# ShieldPi4_WS.net
KiCad netlist of a schematic drawn in EasyEDA
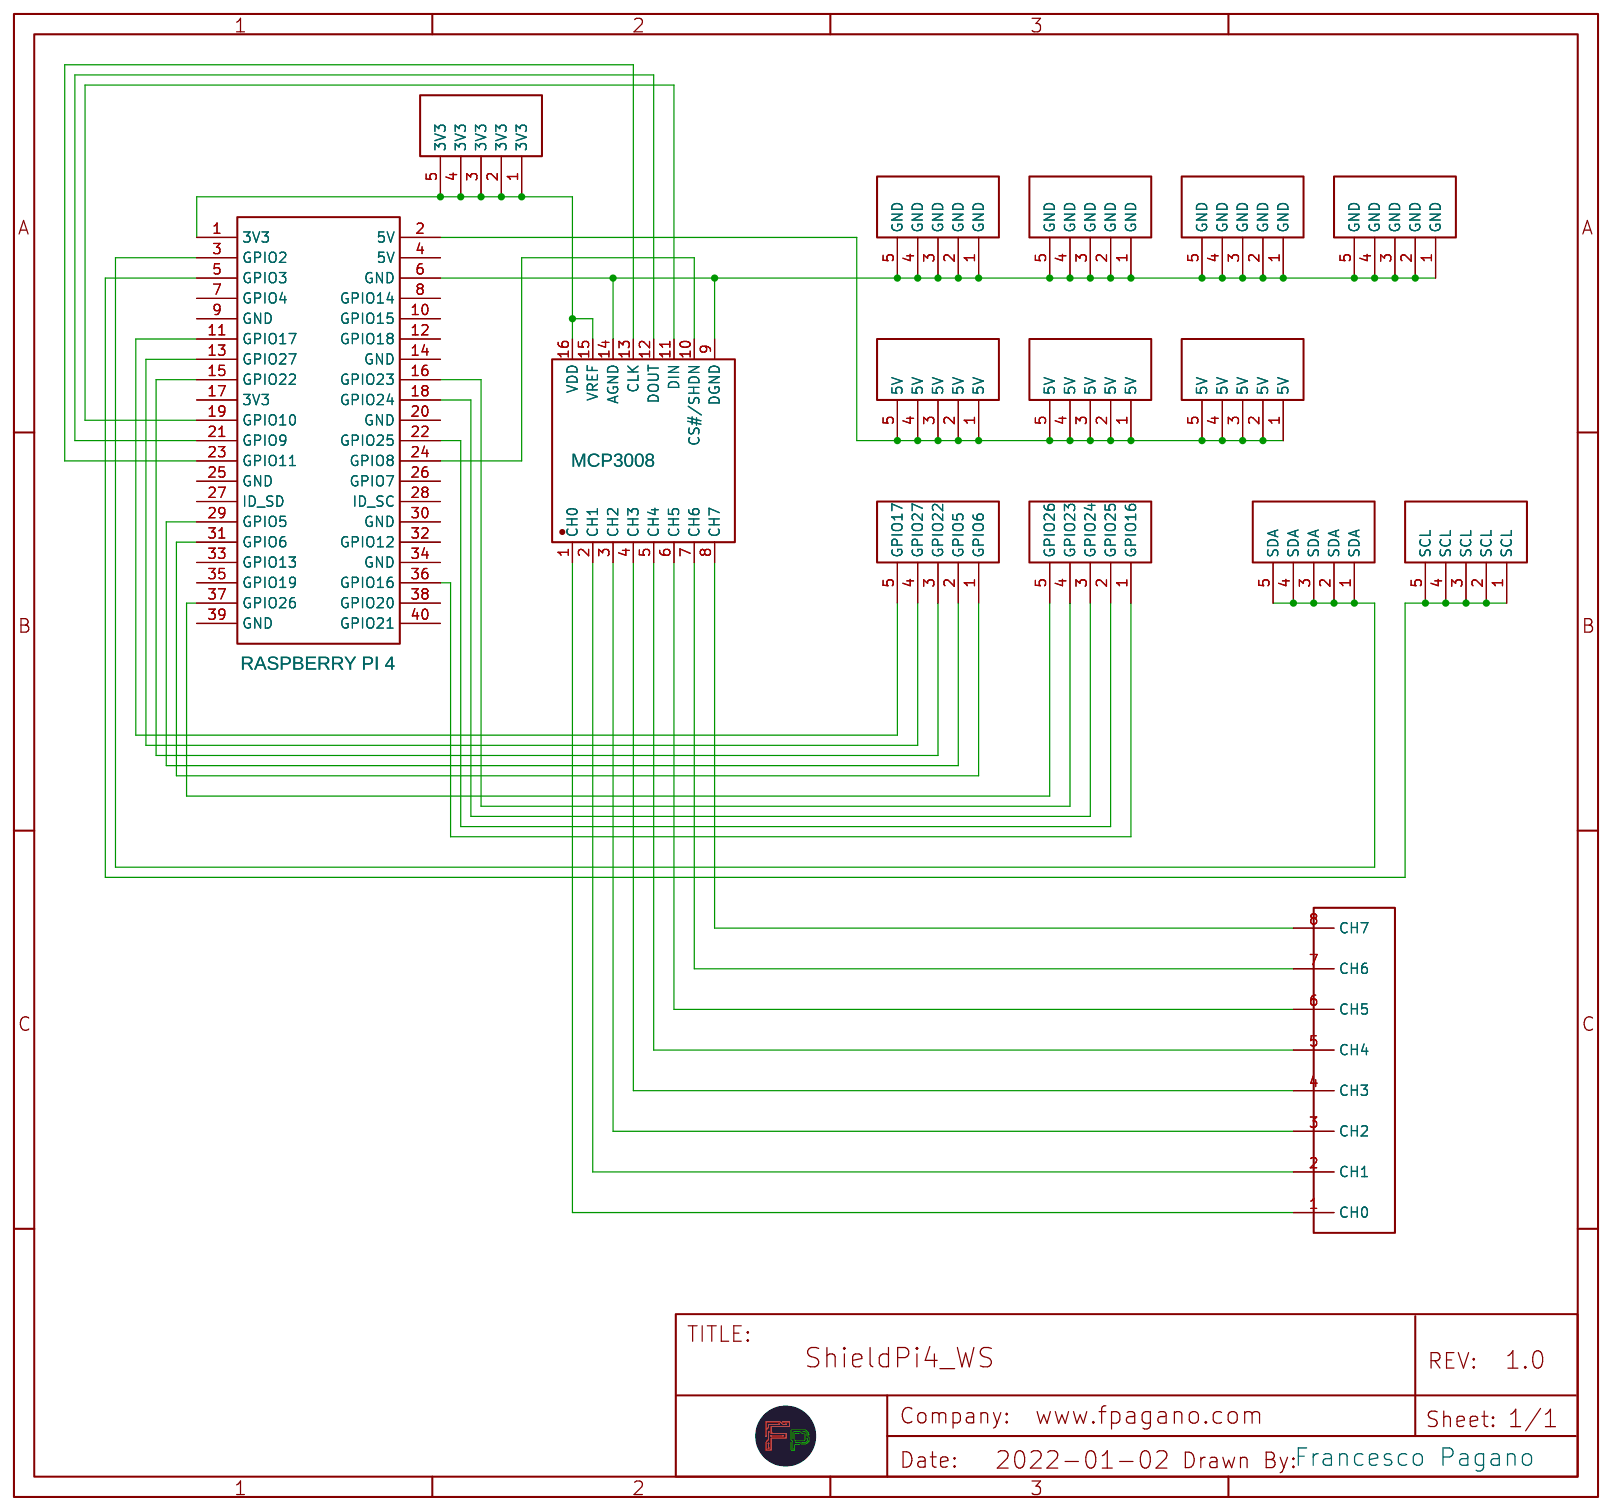
[diagram p0: schematic sheet]

(export (version "E")
  (design (tool "Eeschema 10.0.6"))
  (components
    (comp (ref "U1") (value "RASPBERRY PI 4") (libsource (lib "") (part "RASPBERRY PI 4")))
    (comp (ref "U2") (value "5 Pin Pinheader") (libsource (lib "") (part "5 Pin Pinheader_1")))
    (comp (ref "U3")
      (value "MCP3008")
      (fields
        (field (name "Manufacturer Part") "MCP3008-I/P")
        (field (name "Manufacturer") "MICROCHIP(美国微芯)")
      )
      (libsource (lib "") (part "MCP3008-I/P"))
    )
    (comp (ref "U4") (value "5 Pin Pinheader") (libsource (lib "") (part "5 Pin Pinheader_1")))
    (comp (ref "U5") (value "5 Pin Pinheader") (libsource (lib "") (part "5 Pin Pinheader_2")))
    (comp (ref "U6") (value "5 Pin Pinheader") (libsource (lib "") (part "5 Pin Pinheader_2")))
    (comp (ref "U7") (value "5 Pin Pinheader") (libsource (lib "") (part "5 Pin Pinheader_2")))
    (comp (ref "U8") (value "5 Pin Pinheader") (libsource (lib "") (part "5 Pin Pinheader_6")))
    (comp (ref "U9") (value "5 Pin Pinheader") (libsource (lib "") (part "5 Pin Pinheader_4")))
    (comp (ref "U10") (value "pinheader 2.54 - 8 pins") (libsource (lib "") (part "pinheader 2.54 - 8 pins")))
    (comp (ref "U11") (value "5 Pin Pinheader") (libsource (lib "") (part "5 Pin Pinheader_1")))
    (comp (ref "U12") (value "5 Pin Pinheader") (libsource (lib "") (part "5 Pin Pinheader_5")))
    (comp (ref "U13") (value "5 Pin Pinheader") (libsource (lib "") (part "5 Pin Pinheader_3")))
    (comp (ref "U15") (value "5 Pin Pinheader") (libsource (lib "") (part "5 Pin Pinheader")))
    (comp (ref "U16") (value "5 Pin Pinheader") (libsource (lib "") (part "5 Pin Pinheader_1")))
  )
  (nets
    (net (code "1") (name "Net-(U1-5V-Pad2)") (class "Default")
      (node (ref "U1") (pin "2") (pinfunction "5V_2") (pintype "unspecified"))
      (node (ref "U5") (pin "1") (pinfunction "5V_1") (pintype "unspecified"))
      (node (ref "U5") (pin "2") (pinfunction "5V_2") (pintype "unspecified"))
      (node (ref "U5") (pin "3") (pinfunction "5V_3") (pintype "unspecified"))
      (node (ref "U5") (pin "4") (pinfunction "5V_4") (pintype "unspecified"))
      (node (ref "U5") (pin "5") (pinfunction "5V_5") (pintype "unspecified"))
      (node (ref "U6") (pin "1") (pinfunction "5V_1") (pintype "unspecified"))
      (node (ref "U6") (pin "2") (pinfunction "5V_2") (pintype "unspecified"))
      (node (ref "U6") (pin "3") (pinfunction "5V_3") (pintype "unspecified"))
      (node (ref "U6") (pin "4") (pinfunction "5V_4") (pintype "unspecified"))
      (node (ref "U6") (pin "5") (pinfunction "5V_5") (pintype "unspecified"))
      (node (ref "U7") (pin "1") (pinfunction "5V_1") (pintype "unspecified"))
      (node (ref "U7") (pin "2") (pinfunction "5V_2") (pintype "unspecified"))
      (node (ref "U7") (pin "3") (pinfunction "5V_3") (pintype "unspecified"))
      (node (ref "U7") (pin "4") (pinfunction "5V_4") (pintype "unspecified"))
      (node (ref "U7") (pin "5") (pinfunction "5V_5") (pintype "unspecified"))
    )
    (net (code "2") (name "Net-(U1-GPIO2)") (class "Default")
      (node (ref "U1") (pin "3") (pinfunction "GPIO2_3") (pintype "unspecified"))
      (node (ref "U13") (pin "1") (pinfunction "SDA_1") (pintype "unspecified"))
      (node (ref "U13") (pin "2") (pinfunction "SDA_2") (pintype "unspecified"))
      (node (ref "U13") (pin "3") (pinfunction "SDA_3") (pintype "unspecified"))
      (node (ref "U13") (pin "4") (pinfunction "SDA_4") (pintype "unspecified"))
      (node (ref "U13") (pin "5") (pinfunction "SDA_5") (pintype "unspecified"))
    )
    (net (code "3") (name "Net-(U1-GPIO3)") (class "Default")
      (node (ref "U1") (pin "5") (pinfunction "GPIO3_5") (pintype "unspecified"))
      (node (ref "U12") (pin "1") (pinfunction "SCL_1") (pintype "unspecified"))
      (node (ref "U12") (pin "2") (pinfunction "SCL_2") (pintype "unspecified"))
      (node (ref "U12") (pin "3") (pinfunction "SCL_3") (pintype "unspecified"))
      (node (ref "U12") (pin "4") (pinfunction "SCL_4") (pintype "unspecified"))
      (node (ref "U12") (pin "5") (pinfunction "SCL_5") (pintype "unspecified"))
    )
    (net (code "4") (name "Net-(U1-GPIO5)") (class "Default")
      (node (ref "U1") (pin "29") (pinfunction "GPIO5_29") (pintype "unspecified"))
      (node (ref "U8") (pin "2") (pinfunction "GPIO5_2") (pintype "unspecified"))
    )
    (net (code "5") (name "Net-(U1-GPIO6)") (class "Default")
      (node (ref "U1") (pin "31") (pinfunction "GPIO6_31") (pintype "unspecified"))
      (node (ref "U8") (pin "1") (pinfunction "GPIO6_1") (pintype "unspecified"))
    )
    (net (code "6") (name "Net-(U1-GPIO8)") (class "Default")
      (node (ref "U1") (pin "24") (pinfunction "GPIO8_24") (pintype "unspecified"))
      (node (ref "U3") (pin "10") (pinfunction "CS#/SHDN_10") (pintype "unspecified"))
    )
    (net (code "7") (name "Net-(U1-GPIO9)") (class "Default")
      (node (ref "U1") (pin "21") (pinfunction "GPIO9_21") (pintype "unspecified"))
      (node (ref "U3") (pin "12") (pinfunction "DOUT_12") (pintype "unspecified"))
    )
    (net (code "8") (name "Net-(U1-GPIO10)") (class "Default")
      (node (ref "U1") (pin "19") (pinfunction "GPIO10_19") (pintype "unspecified"))
      (node (ref "U3") (pin "11") (pinfunction "DIN_11") (pintype "unspecified"))
    )
    (net (code "9") (name "Net-(U1-GPIO11)") (class "Default")
      (node (ref "U1") (pin "23") (pinfunction "GPIO11_23") (pintype "unspecified"))
      (node (ref "U3") (pin "13") (pinfunction "CLK_13") (pintype "unspecified"))
    )
    (net (code "10") (name "Net-(U1-GPIO16)") (class "Default")
      (node (ref "U1") (pin "36") (pinfunction "GPIO16_36") (pintype "unspecified"))
      (node (ref "U9") (pin "1") (pinfunction "GPIO16_1") (pintype "unspecified"))
    )
    (net (code "11") (name "Net-(U1-GPIO17)") (class "Default")
      (node (ref "U1") (pin "11") (pinfunction "GPIO17_11") (pintype "unspecified"))
      (node (ref "U8") (pin "5") (pinfunction "GPIO17_5") (pintype "unspecified"))
    )
    (net (code "12") (name "Net-(U1-GPIO22)") (class "Default")
      (node (ref "U1") (pin "15") (pinfunction "GPIO22_15") (pintype "unspecified"))
      (node (ref "U8") (pin "3") (pinfunction "GPIO22_3") (pintype "unspecified"))
    )
    (net (code "13") (name "Net-(U1-GPIO23)") (class "Default")
      (node (ref "U1") (pin "16") (pinfunction "GPIO23_16") (pintype "unspecified"))
      (node (ref "U9") (pin "4") (pinfunction "GPIO23_4") (pintype "unspecified"))
    )
    (net (code "14") (name "Net-(U1-GPIO24)") (class "Default")
      (node (ref "U1") (pin "18") (pinfunction "GPIO24_18") (pintype "unspecified"))
      (node (ref "U9") (pin "3") (pinfunction "GPIO24_3") (pintype "unspecified"))
    )
    (net (code "15") (name "Net-(U1-GPIO25)") (class "Default")
      (node (ref "U1") (pin "22") (pinfunction "GPIO25_22") (pintype "unspecified"))
      (node (ref "U9") (pin "2") (pinfunction "GPIO25_2") (pintype "unspecified"))
    )
    (net (code "16") (name "Net-(U1-GPIO26)") (class "Default")
      (node (ref "U1") (pin "37") (pinfunction "GPIO26_37") (pintype "unspecified"))
      (node (ref "U9") (pin "5") (pinfunction "GPIO26_5") (pintype "unspecified"))
    )
    (net (code "17") (name "Net-(U1-GPIO27)") (class "Default")
      (node (ref "U1") (pin "13") (pinfunction "GPIO27_13") (pintype "unspecified"))
      (node (ref "U8") (pin "4") (pinfunction "GPIO27_4") (pintype "unspecified"))
    )
    (net (code "18") (name "Net-(U3-AGND)") (class "Default")
      (node (ref "U1") (pin "6") (pinfunction "GND_6") (pintype "unspecified"))
      (node (ref "U11") (pin "1") (pinfunction "GND_1") (pintype "unspecified"))
      (node (ref "U11") (pin "2") (pinfunction "GND_2") (pintype "unspecified"))
      (node (ref "U11") (pin "3") (pinfunction "GND_3") (pintype "unspecified"))
      (node (ref "U11") (pin "4") (pinfunction "GND_4") (pintype "unspecified"))
      (node (ref "U11") (pin "5") (pinfunction "GND_5") (pintype "unspecified"))
      (node (ref "U16") (pin "1") (pinfunction "GND_1") (pintype "unspecified"))
      (node (ref "U16") (pin "2") (pinfunction "GND_2") (pintype "unspecified"))
      (node (ref "U16") (pin "3") (pinfunction "GND_3") (pintype "unspecified"))
      (node (ref "U16") (pin "4") (pinfunction "GND_4") (pintype "unspecified"))
      (node (ref "U16") (pin "5") (pinfunction "GND_5") (pintype "unspecified"))
      (node (ref "U2") (pin "1") (pinfunction "GND_1") (pintype "unspecified"))
      (node (ref "U2") (pin "2") (pinfunction "GND_2") (pintype "unspecified"))
      (node (ref "U2") (pin "3") (pinfunction "GND_3") (pintype "unspecified"))
      (node (ref "U2") (pin "4") (pinfunction "GND_4") (pintype "unspecified"))
      (node (ref "U2") (pin "5") (pinfunction "GND_5") (pintype "unspecified"))
      (node (ref "U3") (pin "14") (pinfunction "AGND_14") (pintype "unspecified"))
      (node (ref "U3") (pin "9") (pinfunction "DGND_9") (pintype "unspecified"))
      (node (ref "U4") (pin "1") (pinfunction "GND_1") (pintype "unspecified"))
      (node (ref "U4") (pin "2") (pinfunction "GND_2") (pintype "unspecified"))
      (node (ref "U4") (pin "3") (pinfunction "GND_3") (pintype "unspecified"))
      (node (ref "U4") (pin "4") (pinfunction "GND_4") (pintype "unspecified"))
      (node (ref "U4") (pin "5") (pinfunction "GND_5") (pintype "unspecified"))
    )
    (net (code "19") (name "Net-(U3-VDD)") (class "Default")
      (node (ref "U1") (pin "1") (pinfunction "3V3_1") (pintype "unspecified"))
      (node (ref "U15") (pin "1") (pinfunction "3V3_1") (pintype "unspecified"))
      (node (ref "U15") (pin "2") (pinfunction "3V3_2") (pintype "unspecified"))
      (node (ref "U15") (pin "3") (pinfunction "3V3_3") (pintype "unspecified"))
      (node (ref "U15") (pin "4") (pinfunction "3V3_4") (pintype "unspecified"))
      (node (ref "U15") (pin "5") (pinfunction "3V3_5") (pintype "unspecified"))
      (node (ref "U3") (pin "15") (pinfunction "VREF_15") (pintype "unspecified"))
      (node (ref "U3") (pin "16") (pinfunction "VDD_16") (pintype "unspecified"))
    )
    (net (code "20") (name "Net-(U10-CH0)") (class "Default")
      (node (ref "U10") (pin "1") (pinfunction "CH0_1") (pintype "unspecified"))
      (node (ref "U3") (pin "1") (pinfunction "CH0_1") (pintype "unspecified"))
    )
    (net (code "21") (name "Net-(U10-CH1)") (class "Default")
      (node (ref "U10") (pin "2") (pinfunction "CH1_2") (pintype "unspecified"))
      (node (ref "U3") (pin "2") (pinfunction "CH1_2") (pintype "unspecified"))
    )
    (net (code "22") (name "Net-(U10-CH2)") (class "Default")
      (node (ref "U10") (pin "3") (pinfunction "CH2_3") (pintype "unspecified"))
      (node (ref "U3") (pin "3") (pinfunction "CH2_3") (pintype "unspecified"))
    )
    (net (code "23") (name "Net-(U10-CH3)") (class "Default")
      (node (ref "U10") (pin "4") (pinfunction "CH3_4") (pintype "unspecified"))
      (node (ref "U3") (pin "4") (pinfunction "CH3_4") (pintype "unspecified"))
    )
    (net (code "24") (name "Net-(U10-CH4)") (class "Default")
      (node (ref "U10") (pin "5") (pinfunction "CH4_5") (pintype "unspecified"))
      (node (ref "U3") (pin "5") (pinfunction "CH4_5") (pintype "unspecified"))
    )
    (net (code "25") (name "Net-(U10-CH5)") (class "Default")
      (node (ref "U10") (pin "6") (pinfunction "CH5_6") (pintype "unspecified"))
      (node (ref "U3") (pin "6") (pinfunction "CH5_6") (pintype "unspecified"))
    )
    (net (code "26") (name "Net-(U10-CH6)") (class "Default")
      (node (ref "U10") (pin "7") (pinfunction "CH6_7") (pintype "unspecified"))
      (node (ref "U3") (pin "7") (pinfunction "CH6_7") (pintype "unspecified"))
    )
    (net (code "27") (name "Net-(U10-CH7)") (class "Default")
      (node (ref "U10") (pin "8") (pinfunction "CH7_8") (pintype "unspecified"))
      (node (ref "U3") (pin "8") (pinfunction "CH7_8") (pintype "unspecified"))
    )
    (net (code "28") (name "unconnected-(U1-3V3-Pad17)") (class "Default")
      (node (ref "U1") (pin "17") (pinfunction "3V3_17") (pintype "unspecified"))
    )
    (net (code "29") (name "unconnected-(U1-5V-Pad4)") (class "Default")
      (node (ref "U1") (pin "4") (pinfunction "5V_4") (pintype "unspecified"))
    )
    (net (code "30") (name "unconnected-(U1-GND-Pad9)") (class "Default")
      (node (ref "U1") (pin "9") (pinfunction "GND_9") (pintype "unspecified"))
    )
    (net (code "31") (name "unconnected-(U1-GND-Pad14)") (class "Default")
      (node (ref "U1") (pin "14") (pinfunction "GND_14") (pintype "unspecified"))
    )
    (net (code "32") (name "unconnected-(U1-GND-Pad20)") (class "Default")
      (node (ref "U1") (pin "20") (pinfunction "GND_20") (pintype "unspecified"))
    )
    (net (code "33") (name "unconnected-(U1-GND-Pad25)") (class "Default")
      (node (ref "U1") (pin "25") (pinfunction "GND_25") (pintype "unspecified"))
    )
    (net (code "34") (name "unconnected-(U1-GND-Pad30)") (class "Default")
      (node (ref "U1") (pin "30") (pinfunction "GND_30") (pintype "unspecified"))
    )
    (net (code "35") (name "unconnected-(U1-GND-Pad34)") (class "Default")
      (node (ref "U1") (pin "34") (pinfunction "GND_34") (pintype "unspecified"))
    )
    (net (code "36") (name "unconnected-(U1-GND-Pad39)") (class "Default")
      (node (ref "U1") (pin "39") (pinfunction "GND_39") (pintype "unspecified"))
    )
    (net (code "37") (name "unconnected-(U1-GPIO4-Pad7)") (class "Default")
      (node (ref "U1") (pin "7") (pinfunction "GPIO4_7") (pintype "unspecified"))
    )
    (net (code "38") (name "unconnected-(U1-GPIO7-Pad26)") (class "Default")
      (node (ref "U1") (pin "26") (pinfunction "GPIO7_26") (pintype "unspecified"))
    )
    (net (code "39") (name "unconnected-(U1-GPIO12-Pad32)") (class "Default")
      (node (ref "U1") (pin "32") (pinfunction "GPIO12_32") (pintype "unspecified"))
    )
    (net (code "40") (name "unconnected-(U1-GPIO13-Pad33)") (class "Default")
      (node (ref "U1") (pin "33") (pinfunction "GPIO13_33") (pintype "unspecified"))
    )
    (net (code "41") (name "unconnected-(U1-GPIO14-Pad8)") (class "Default")
      (node (ref "U1") (pin "8") (pinfunction "GPIO14_8") (pintype "unspecified"))
    )
    (net (code "42") (name "unconnected-(U1-GPIO15-Pad10)") (class "Default")
      (node (ref "U1") (pin "10") (pinfunction "GPIO15_10") (pintype "unspecified"))
    )
    (net (code "43") (name "unconnected-(U1-GPIO18-Pad12)") (class "Default")
      (node (ref "U1") (pin "12") (pinfunction "GPIO18_12") (pintype "unspecified"))
    )
    (net (code "44") (name "unconnected-(U1-GPIO19-Pad35)") (class "Default")
      (node (ref "U1") (pin "35") (pinfunction "GPIO19_35") (pintype "unspecified"))
    )
    (net (code "45") (name "unconnected-(U1-GPIO20-Pad38)") (class "Default")
      (node (ref "U1") (pin "38") (pinfunction "GPIO20_38") (pintype "unspecified"))
    )
    (net (code "46") (name "unconnected-(U1-GPIO21-Pad40)") (class "Default")
      (node (ref "U1") (pin "40") (pinfunction "GPIO21_40") (pintype "unspecified"))
    )
    (net (code "47") (name "unconnected-(U1-ID_SC-Pad28)") (class "Default")
      (node (ref "U1") (pin "28") (pinfunction "ID_SC_28") (pintype "unspecified"))
    )
    (net (code "48") (name "unconnected-(U1-ID_SD-Pad27)") (class "Default")
      (node (ref "U1") (pin "27") (pinfunction "ID_SD_27") (pintype "unspecified"))
    )
  )
)
